# V1_3.net
KiCad netlist of a schematic drawn in Altium Designer
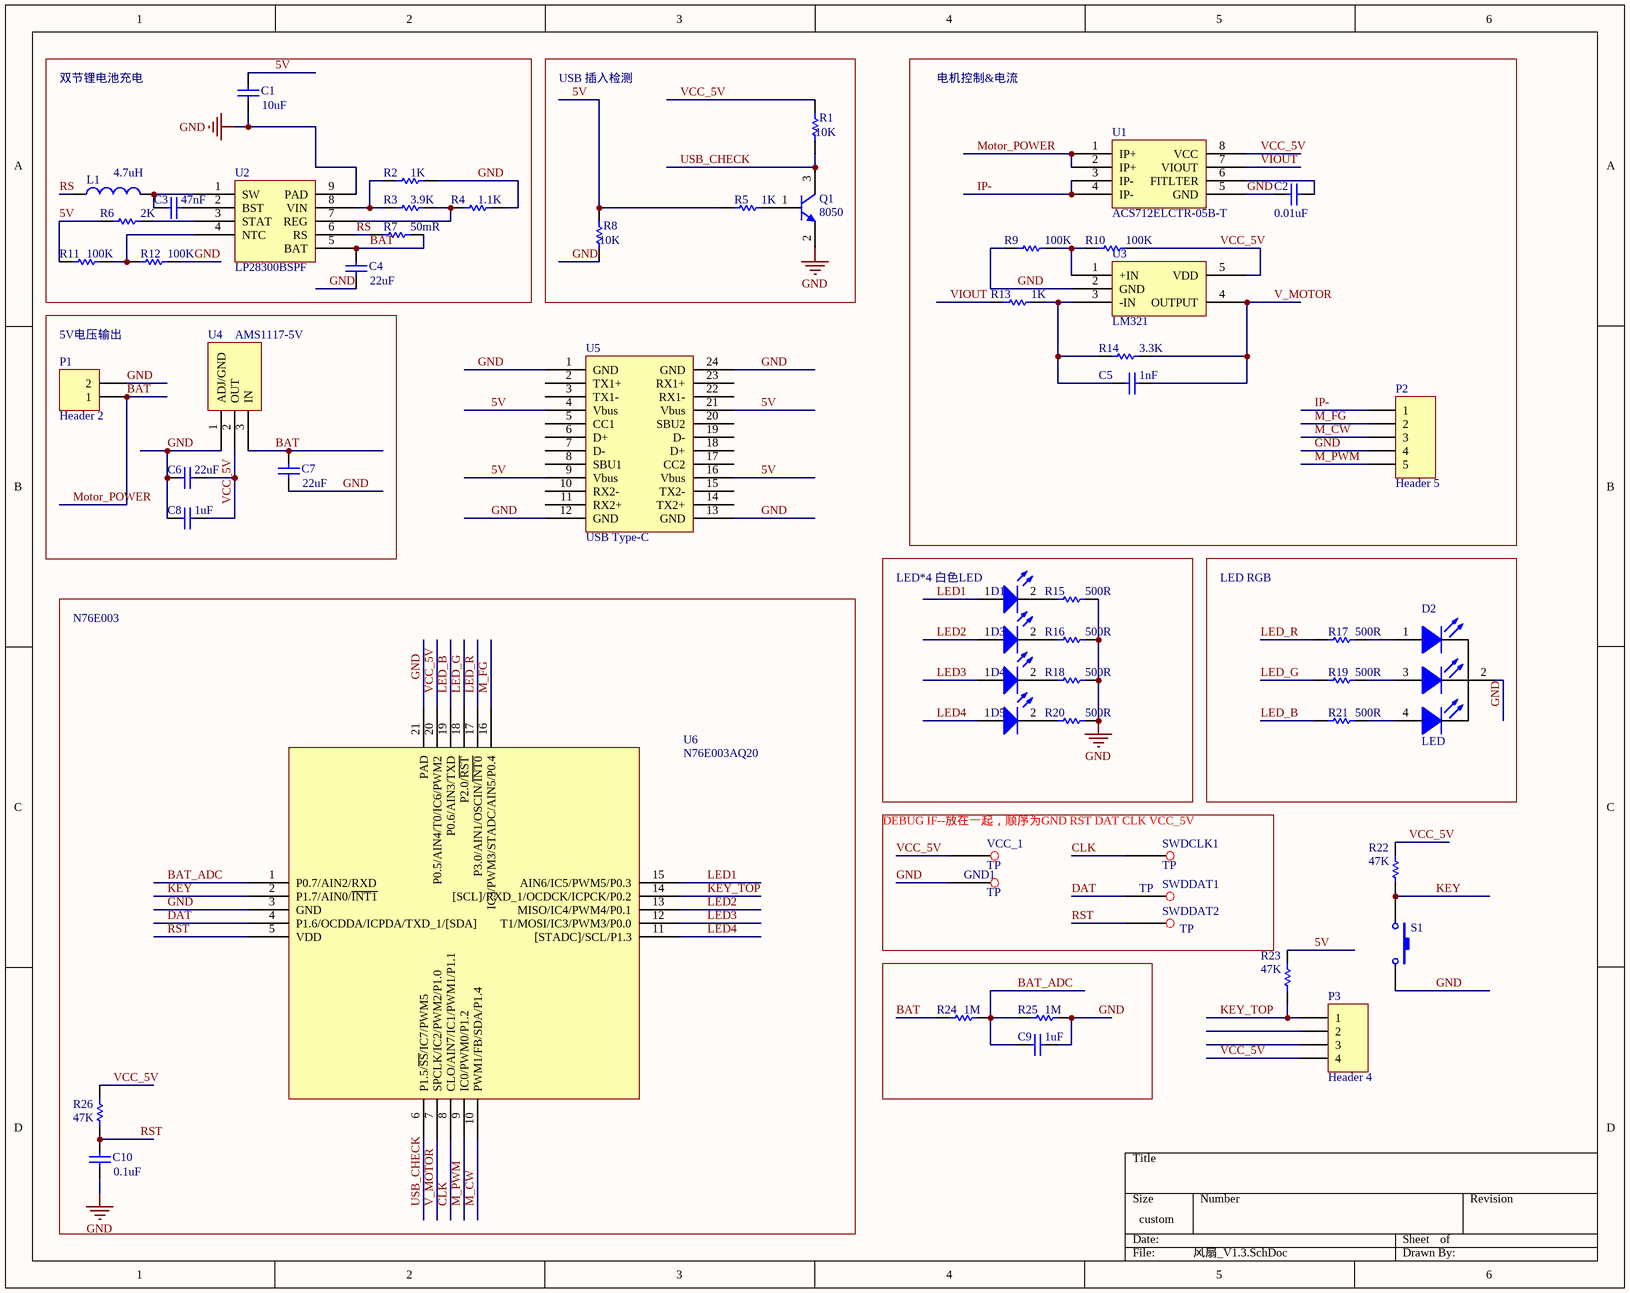
[diagram p0: 风扇_V1.3.SchDoc]

(export (version "E")
  (design (tool "Eeschema 10.0.6"))
  (components
    (comp (ref "C1")
      (value "10uF")
      (footprint "C-0805")
      (description "Capacitor")
      (fields (field (name "PUBLISHER") "Altium Limited"))
      (libsource (lib "Miscellaneous Devices") (part "Cap"))
    )
    (comp (ref "C2")
      (value "0.01uF")
      (footprint "C-0603")
      (description "Capacitor")
      (fields (field (name "PUBLISHER") "Altium Limited"))
      (libsource (lib "Miscellaneous Devices") (part "Cap"))
    )
    (comp (ref "C3")
      (value "47nF")
      (footprint "C-0603")
      (description "Capacitor")
      (fields (field (name "PUBLISHER") "Altium Limited"))
      (libsource (lib "Miscellaneous Devices") (part "Cap"))
    )
    (comp (ref "C4")
      (value "22uF")
      (footprint "C-0805")
      (description "Capacitor")
      (fields (field (name "PUBLISHER") "Altium Limited"))
      (libsource (lib "Miscellaneous Devices") (part "Cap"))
    )
    (comp (ref "C5")
      (value "1nF")
      (footprint "C-0603")
      (description "Capacitor")
      (fields (field (name "PUBLISHER") "Altium Limited"))
      (libsource (lib "Miscellaneous Devices") (part "Cap"))
    )
    (comp (ref "C6")
      (value "22uF")
      (footprint "C-0805")
      (description "Capacitor")
      (fields (field (name "PUBLISHER") "Altium Limited"))
      (libsource (lib "Miscellaneous Devices") (part "Cap"))
    )
    (comp (ref "C7")
      (value "22uF")
      (footprint "C-0805")
      (description "Capacitor")
      (fields (field (name "PUBLISHER") "Altium Limited"))
      (libsource (lib "Miscellaneous Devices") (part "Cap"))
    )
    (comp (ref "C8")
      (value "1uF")
      (footprint "C-0603")
      (description "Capacitor")
      (fields (field (name "PUBLISHER") "Altium Limited"))
      (libsource (lib "Miscellaneous Devices") (part "Cap"))
    )
    (comp (ref "C9")
      (value "1uF")
      (footprint "C-0603")
      (description "Capacitor")
      (fields (field (name "PUBLISHER") "Altium Limited"))
      (libsource (lib "Miscellaneous Devices") (part "Cap"))
    )
    (comp (ref "C10")
      (value "0.1uF")
      (footprint "C-0603")
      (description "Capacitor")
      (fields (field (name "PUBLISHER") "Altium Limited"))
      (libsource (lib "Miscellaneous Devices") (part "Cap"))
    )
    (comp (ref "D1")
      (value "LED0")
      (footprint "LED-0603")
      (description "Typical INFRARED GaAs LED")
      (fields (field (name "PUBLISHER") "Altium Limited"))
      (libsource (lib "Miscellaneous Devices") (part "LED0"))
    )
    (comp (ref "D2") (value "LED") (footprint "0603*2-LED") (libsource (lib "SA2") (part "LED")))
    (comp (ref "D3")
      (value "LED0")
      (footprint "LED-0603")
      (description "Typical INFRARED GaAs LED")
      (fields (field (name "PUBLISHER") "Altium Limited"))
      (libsource (lib "Miscellaneous Devices") (part "LED0"))
    )
    (comp (ref "D4")
      (value "LED0")
      (footprint "LED-0603")
      (description "Typical INFRARED GaAs LED")
      (fields (field (name "PUBLISHER") "Altium Limited"))
      (libsource (lib "Miscellaneous Devices") (part "LED0"))
    )
    (comp (ref "D5")
      (value "LED0")
      (footprint "LED-0603")
      (description "Typical INFRARED GaAs LED")
      (fields (field (name "PUBLISHER") "Altium Limited"))
      (libsource (lib "Miscellaneous Devices") (part "LED0"))
    )
    (comp (ref "GND1") (value "TP") (footprint "TP-1.5") (libsource (lib "Others_IC_SCH_LIB") (part "TP")))
    (comp (ref "L1")
      (value "4.7uH")
      (footprint "L-SMD")
      (description "Inductor")
      (fields (field (name "PUBLISHER") "Altium Limited"))
      (libsource (lib "Miscellaneous Devices") (part "Inductor"))
    )
    (comp (ref "P1")
      (value "Header 2")
      (footprint "HDR1X2")
      (description "Header, 2-Pin")
      (fields (field (name "PUBLISHER") "Altium Limited"))
      (libsource (lib "Miscellaneous Connectors") (part "Header 2"))
    )
    (comp (ref "P2")
      (value "Header 5")
      (footprint "HDR1X5")
      (description "Header, 5-Pin")
      (fields (field (name "PUBLISHER") "Altium Limited"))
      (libsource (lib "Miscellaneous Connectors") (part "Header 5"))
    )
    (comp (ref "P3")
      (value "Header 4")
      (footprint "HDR1X4")
      (description "Header, 4-Pin")
      (fields (field (name "PUBLISHER") "Altium Limited"))
      (libsource (lib "Miscellaneous Connectors") (part "Header 4"))
    )
    (comp (ref "Q1")
      (value "8050")
      (footprint "SOT-23")
      (description "NPN Bipolar Transistor")
      (fields (field (name "PUBLISHER") "Altium Limited"))
      (libsource (lib "Miscellaneous Devices") (part "NPN"))
    )
    (comp (ref "R1")
      (value "10K")
      (footprint "R-0603")
      (description "Resistor")
      (fields (field (name "PUBLISHER") "Altium Limited"))
      (libsource (lib "Miscellaneous Devices") (part "Res1"))
    )
    (comp (ref "R2")
      (value "1K")
      (footprint "R-0603")
      (description "Resistor")
      (fields (field (name "PUBLISHER") "Altium Limited"))
      (libsource (lib "Miscellaneous Devices") (part "Res1"))
    )
    (comp (ref "R3")
      (value "3.9K")
      (footprint "R-0603")
      (description "Resistor")
      (fields (field (name "PUBLISHER") "Altium Limited"))
      (libsource (lib "Miscellaneous Devices") (part "Res1"))
    )
    (comp (ref "R4")
      (value "1.1K")
      (footprint "R-0603")
      (description "Resistor")
      (fields (field (name "PUBLISHER") "Altium Limited"))
      (libsource (lib "Miscellaneous Devices") (part "Res1"))
    )
    (comp (ref "R5")
      (value "1K")
      (footprint "R-0603")
      (description "Resistor")
      (fields (field (name "PUBLISHER") "Altium Limited"))
      (libsource (lib "Miscellaneous Devices") (part "Res1"))
    )
    (comp (ref "R6")
      (value "2K")
      (footprint "R-0603")
      (description "Resistor")
      (fields (field (name "PUBLISHER") "Altium Limited"))
      (libsource (lib "Miscellaneous Devices") (part "Res1"))
    )
    (comp (ref "R7")
      (value "50mR")
      (footprint "R-0603")
      (description "Resistor")
      (fields (field (name "PUBLISHER") "Altium Limited"))
      (libsource (lib "Miscellaneous Devices") (part "Res1"))
    )
    (comp (ref "R8")
      (value "10K")
      (footprint "R-0603")
      (description "Resistor")
      (fields (field (name "PUBLISHER") "Altium Limited"))
      (libsource (lib "Miscellaneous Devices") (part "Res1"))
    )
    (comp (ref "R9")
      (value "100K")
      (footprint "R-0603")
      (description "Resistor")
      (fields (field (name "PUBLISHER") "Altium Limited"))
      (libsource (lib "Miscellaneous Devices") (part "Res1"))
    )
    (comp (ref "R10")
      (value "100K")
      (footprint "R-0603")
      (description "Resistor")
      (fields (field (name "PUBLISHER") "Altium Limited"))
      (libsource (lib "Miscellaneous Devices") (part "Res1"))
    )
    (comp (ref "R11")
      (value "100K")
      (footprint "R-0603")
      (description "Resistor")
      (fields (field (name "PUBLISHER") "Altium Limited"))
      (libsource (lib "Miscellaneous Devices") (part "Res1"))
    )
    (comp (ref "R12")
      (value "100K")
      (footprint "R-0603")
      (description "Resistor")
      (fields (field (name "PUBLISHER") "Altium Limited"))
      (libsource (lib "Miscellaneous Devices") (part "Res1"))
    )
    (comp (ref "R13")
      (value "1K")
      (footprint "R-0603")
      (description "Resistor")
      (fields (field (name "PUBLISHER") "Altium Limited"))
      (libsource (lib "Miscellaneous Devices") (part "Res1"))
    )
    (comp (ref "R14")
      (value "3.3K")
      (footprint "R-0603")
      (description "Resistor")
      (fields (field (name "PUBLISHER") "Altium Limited"))
      (libsource (lib "Miscellaneous Devices") (part "Res1"))
    )
    (comp (ref "R15")
      (value "500R")
      (footprint "R-0603")
      (description "Resistor")
      (fields (field (name "PUBLISHER") "Altium Limited"))
      (libsource (lib "Miscellaneous Devices") (part "Res1"))
    )
    (comp (ref "R16")
      (value "500R")
      (footprint "R-0603")
      (description "Resistor")
      (fields (field (name "PUBLISHER") "Altium Limited"))
      (libsource (lib "Miscellaneous Devices") (part "Res1"))
    )
    (comp (ref "R17")
      (value "500R")
      (footprint "R-0603")
      (description "Resistor")
      (fields (field (name "PUBLISHER") "Altium Limited"))
      (libsource (lib "Miscellaneous Devices") (part "Res1"))
    )
    (comp (ref "R18")
      (value "500R")
      (footprint "R-0603")
      (description "Resistor")
      (fields (field (name "PUBLISHER") "Altium Limited"))
      (libsource (lib "Miscellaneous Devices") (part "Res1"))
    )
    (comp (ref "R19")
      (value "500R")
      (footprint "R-0603")
      (description "Resistor")
      (fields (field (name "PUBLISHER") "Altium Limited"))
      (libsource (lib "Miscellaneous Devices") (part "Res1"))
    )
    (comp (ref "R20")
      (value "500R")
      (footprint "R-0603")
      (description "Resistor")
      (fields (field (name "PUBLISHER") "Altium Limited"))
      (libsource (lib "Miscellaneous Devices") (part "Res1"))
    )
    (comp (ref "R21")
      (value "500R")
      (footprint "R-0603")
      (description "Resistor")
      (fields (field (name "PUBLISHER") "Altium Limited"))
      (libsource (lib "Miscellaneous Devices") (part "Res1"))
    )
    (comp (ref "R22")
      (value "47K")
      (footprint "R-0603")
      (description "Resistor")
      (fields (field (name "PUBLISHER") "Altium Limited"))
      (libsource (lib "Miscellaneous Devices") (part "Res1"))
    )
    (comp (ref "R23")
      (value "47K")
      (footprint "R-0603")
      (description "Resistor")
      (fields (field (name "PUBLISHER") "Altium Limited"))
      (libsource (lib "Miscellaneous Devices") (part "Res1"))
    )
    (comp (ref "R24")
      (value "1M")
      (footprint "R-0603")
      (description "Resistor")
      (fields (field (name "PUBLISHER") "Altium Limited"))
      (libsource (lib "Miscellaneous Devices") (part "Res1"))
    )
    (comp (ref "R25")
      (value "1M")
      (footprint "R-0603")
      (description "Resistor")
      (fields (field (name "PUBLISHER") "Altium Limited"))
      (libsource (lib "Miscellaneous Devices") (part "Res1"))
    )
    (comp (ref "R26")
      (value "47K")
      (footprint "R-0603")
      (description "Resistor")
      (fields (field (name "PUBLISHER") "Altium Limited"))
      (libsource (lib "Miscellaneous Devices") (part "Res1"))
    )
    (comp (ref "S1")
      (value "SW-PB")
      (footprint "SW-6*6*4.3")
      (description "Switch")
      (fields (field (name "PUBLISHER") "Altium Limited"))
      (libsource (lib "Miscellaneous Devices") (part "SW-PB"))
    )
    (comp (ref "SWDCLK1") (value "TP") (footprint "TP-1.5") (libsource (lib "Others_IC_SCH_LIB") (part "TP")))
    (comp (ref "SWDDAT1") (value "TP") (footprint "TP-1.5") (libsource (lib "Others_IC_SCH_LIB") (part "TP")))
    (comp (ref "SWDDAT2") (value "TP") (footprint "TP-1.5") (libsource (lib "Others_IC_SCH_LIB") (part "TP")))
    (comp (ref "U1")
      (value "ACS712ELCTR-05B-T")
      (footprint "SOIC8")
      (libsource (lib "Others_IC_SCH_LIB") (part "ACS712ELCTR-05B-T"))
    )
    (comp (ref "U2")
      (value "LP28300BSPF")
      (footprint "ESOP8")
      (libsource (lib "Others_IC_SCH_LIB") (part "LP28300BSPF"))
    )
    (comp (ref "U3")
      (value "LM321")
      (footprint "SOT-23-5")
      (libsource (lib "Others_IC_SCH_LIB") (part "LM321"))
    )
    (comp (ref "U4")
      (value "AMS1117-5V")
      (footprint "SOT-223")
      (libsource (lib "Others_IC_SCH_LIB") (part "AMS1117"))
    )
    (comp (ref "U5")
      (value "USB Type-C")
      (footprint "USB-type C")
      (libsource (lib "Others_IC_SCH_LIB") (part "USB Type-C"))
    )
    (comp (ref "U6")
      (value "N76E003AQ20")
      (footprint "QFN-20 0.4mm")
      (libsource (lib "Others_IC_SCH_LIB") (part "N76E003AQ20"))
    )
    (comp (ref "VCC_1") (value "TP") (footprint "TP-1.5") (libsource (lib "Others_IC_SCH_LIB") (part "TP")))
  )
  (nets
    (net (code "1") (name "/5V") (class "Default")
      (node (ref "C1") (pin "1") (pinfunction "1_1") (pintype "passive"))
      (node (ref "R11") (pin "2") (pinfunction "2_2") (pintype "passive"))
      (node (ref "R23") (pin "2") (pinfunction "2_2") (pintype "passive"))
      (node (ref "R5") (pin "1") (pinfunction "1_1") (pintype "passive"))
      (node (ref "R6") (pin "2") (pinfunction "2_2") (pintype "passive"))
      (node (ref "R8") (pin "1") (pinfunction "1_1") (pintype "passive"))
      (node (ref "U5") (pin "16") (pinfunction "Vbus_16") (pintype "passive"))
      (node (ref "U5") (pin "21") (pinfunction "Vbus_21") (pintype "passive"))
      (node (ref "U5") (pin "4") (pinfunction "Vbus_4") (pintype "passive"))
      (node (ref "U5") (pin "9") (pinfunction "Vbus_9") (pintype "passive"))
    )
    (net (code "2") (name "/BAT") (class "Default")
      (node (ref "C4") (pin "1") (pinfunction "1_1") (pintype "passive"))
      (node (ref "C7") (pin "2") (pinfunction "2_2") (pintype "passive"))
      (node (ref "P1") (pin "1") (pinfunction "1_1") (pintype "passive"))
      (node (ref "R24") (pin "1") (pinfunction "1_1") (pintype "passive"))
      (node (ref "R7") (pin "1") (pinfunction "1_1") (pintype "passive"))
      (node (ref "U1") (pin "1") (pinfunction "IP+_1") (pintype "passive"))
      (node (ref "U1") (pin "2") (pinfunction "IP+_2") (pintype "passive"))
      (node (ref "U2") (pin "5") (pinfunction "BAT_5") (pintype "passive"))
      (node (ref "U4") (pin "3") (pinfunction "IN_3") (pintype "passive"))
    )
    (net (code "3") (name "/BAT_ADC") (class "Default")
      (node (ref "C9") (pin "2") (pinfunction "2_2") (pintype "passive"))
      (node (ref "R24") (pin "2") (pinfunction "2_2") (pintype "passive"))
      (node (ref "R25") (pin "1") (pinfunction "1_1") (pintype "passive"))
      (node (ref "U6") (pin "1") (pinfunction "P0.7/AIN2/RXD_1") (pintype "passive"))
    )
    (net (code "4") (name "/CLK") (class "Default")
      (node (ref "SWDCLK1") (pin "1") (pinfunction "1_1") (pintype "passive"))
      (node (ref "U6") (pin "8") (pinfunction "CLO/AIN7/IC1/PWM1/P1.1_8") (pintype "passive"))
    )
    (net (code "5") (name "/DAT") (class "Default")
      (node (ref "SWDDAT1") (pin "1") (pinfunction "1_1") (pintype "passive"))
      (node (ref "U6") (pin "4") (pinfunction "P1.6/OCDDA/ICPDA/TXD_1/[SDA]_4") (pintype "passive"))
    )
    (net (code "6") (name "/IP-") (class "Default")
      (node (ref "P2") (pin "1") (pinfunction "1_1") (pintype "passive"))
      (node (ref "U1") (pin "3") (pinfunction "IP-_3") (pintype "passive"))
      (node (ref "U1") (pin "4") (pinfunction "IP-_4") (pintype "passive"))
    )
    (net (code "7") (name "/KEY") (class "Default")
      (node (ref "R22") (pin "1") (pinfunction "1_1") (pintype "passive"))
      (node (ref "S1") (pin "1") (pinfunction "1_1") (pintype "passive"))
      (node (ref "U6") (pin "2") (pinfunction "P1.7/AIN0/~{INT1}_2") (pintype "passive"))
    )
    (net (code "8") (name "/KEY_TOP") (class "Default")
      (node (ref "P3") (pin "1") (pinfunction "1_1") (pintype "passive"))
      (node (ref "R23") (pin "1") (pinfunction "1_1") (pintype "passive"))
      (node (ref "U6") (pin "14") (pinfunction "[SCL]/RXD_1/OCDCK/ICPCK/P0.2_14") (pintype "passive"))
    )
    (net (code "9") (name "/LED1") (class "Default")
      (node (ref "D1") (pin "1") (pinfunction "A_1") (pintype "passive"))
      (node (ref "U6") (pin "15") (pinfunction "AIN6/IC5/PWM5/P0.3_15") (pintype "passive"))
    )
    (net (code "10") (name "/LED2") (class "Default")
      (node (ref "D3") (pin "1") (pinfunction "A_1") (pintype "passive"))
      (node (ref "U6") (pin "13") (pinfunction "MISO/IC4/PWM4/P0.1_13") (pintype "passive"))
    )
    (net (code "11") (name "/LED3") (class "Default")
      (node (ref "D4") (pin "1") (pinfunction "A_1") (pintype "passive"))
      (node (ref "U6") (pin "12") (pinfunction "T1/MOSI/IC3/PWM3/P0.0_12") (pintype "passive"))
    )
    (net (code "12") (name "/LED4") (class "Default")
      (node (ref "D5") (pin "1") (pinfunction "A_1") (pintype "passive"))
      (node (ref "U6") (pin "11") (pinfunction "[STADC]/SCL/P1.3_11") (pintype "passive"))
    )
    (net (code "13") (name "/LED_B") (class "Default")
      (node (ref "R21") (pin "1") (pinfunction "1_1") (pintype "passive"))
      (node (ref "U6") (pin "19") (pinfunction "P0.6/AIN3/TXD_19") (pintype "passive"))
    )
    (net (code "14") (name "/LED_G") (class "Default")
      (node (ref "R19") (pin "1") (pinfunction "1_1") (pintype "passive"))
      (node (ref "U6") (pin "18") (pinfunction "P2.0/~{RST}_18") (pintype "passive"))
    )
    (net (code "15") (name "/LED_R") (class "Default")
      (node (ref "R17") (pin "1") (pinfunction "1_1") (pintype "passive"))
      (node (ref "U6") (pin "17") (pinfunction "P3.0/AIN1/OSCIN/~{INT0}_17") (pintype "passive"))
    )
    (net (code "16") (name "/M_CW") (class "Default")
      (node (ref "P2") (pin "3") (pinfunction "3_3") (pintype "passive"))
      (node (ref "U6") (pin "10") (pinfunction "PWM1/FB/SDA/P1.4_10") (pintype "passive"))
    )
    (net (code "17") (name "/M_FG") (class "Default")
      (node (ref "P2") (pin "2") (pinfunction "2_2") (pintype "passive"))
      (node (ref "U6") (pin "16") (pinfunction "IC3/PWM3/STADC/AIN5/P0.4_16") (pintype "passive"))
    )
    (net (code "18") (name "/M_PWM") (class "Default")
      (node (ref "P2") (pin "5") (pinfunction "5_5") (pintype "passive"))
      (node (ref "U6") (pin "9") (pinfunction "IC0/PWM0/P1.2_9") (pintype "passive"))
    )
    (net (code "19") (name "/RS") (class "Default")
      (node (ref "L1") (pin "1") (pinfunction "1_1") (pintype "passive"))
      (node (ref "R7") (pin "2") (pinfunction "2_2") (pintype "passive"))
      (node (ref "U2") (pin "6") (pinfunction "RS_6") (pintype "passive"))
    )
    (net (code "20") (name "/RST") (class "Default")
      (node (ref "C10") (pin "2") (pinfunction "2_2") (pintype "passive"))
      (node (ref "R26") (pin "1") (pinfunction "1_1") (pintype "passive"))
      (node (ref "SWDDAT2") (pin "1") (pinfunction "1_1") (pintype "passive"))
      (node (ref "U6") (pin "5") (pinfunction "VDD_5") (pintype "passive"))
    )
    (net (code "21") (name "/USB_CHECK") (class "Default")
      (node (ref "Q1") (pin "3") (pinfunction "C_3") (pintype "passive"))
      (node (ref "R1") (pin "1") (pinfunction "1_1") (pintype "passive"))
      (node (ref "U6") (pin "6") (pinfunction "P1.5/~{SS}/IC7/PWM5_6") (pintype "passive"))
    )
    (net (code "22") (name "/VCC_5V") (class "Default")
      (node (ref "C6") (pin "2") (pinfunction "2_2") (pintype "passive"))
      (node (ref "C8") (pin "2") (pinfunction "2_2") (pintype "passive"))
      (node (ref "P3") (pin "4") (pinfunction "4_4") (pintype "passive"))
      (node (ref "R1") (pin "2") (pinfunction "2_2") (pintype "passive"))
      (node (ref "R10") (pin "2") (pinfunction "2_2") (pintype "passive"))
      (node (ref "R22") (pin "2") (pinfunction "2_2") (pintype "passive"))
      (node (ref "R26") (pin "2") (pinfunction "2_2") (pintype "passive"))
      (node (ref "U1") (pin "8") (pinfunction "VCC_8") (pintype "passive"))
      (node (ref "U3") (pin "5") (pinfunction "VDD_5") (pintype "passive"))
      (node (ref "U4") (pin "2") (pinfunction "OUT_2") (pintype "passive"))
      (node (ref "U6") (pin "20") (pinfunction "P0.5/AIN4/T0/IC6/PWM2_20") (pintype "passive"))
      (node (ref "VCC_1") (pin "1") (pinfunction "1_1") (pintype "passive"))
    )
    (net (code "23") (name "/VIOUT") (class "Default")
      (node (ref "R13") (pin "1") (pinfunction "1_1") (pintype "passive"))
      (node (ref "U1") (pin "7") (pinfunction "VIOUT_7") (pintype "passive"))
    )
    (net (code "24") (name "/V_MOTOR") (class "Default")
      (node (ref "C5") (pin "1") (pinfunction "1_1") (pintype "passive"))
      (node (ref "R14") (pin "2") (pinfunction "2_2") (pintype "passive"))
      (node (ref "U3") (pin "4") (pinfunction "OUTPUT_4") (pintype "passive"))
      (node (ref "U6") (pin "7") (pinfunction "SPCLK/IC2/PWM2/P1.0_7") (pintype "passive"))
    )
    (net (code "25") (name "GND") (class "Default")
      (node (ref "C1") (pin "2") (pinfunction "2_2") (pintype "passive"))
      (node (ref "C10") (pin "1") (pinfunction "1_1") (pintype "passive"))
      (node (ref "C2") (pin "2") (pinfunction "2_2") (pintype "passive"))
      (node (ref "C4") (pin "2") (pinfunction "2_2") (pintype "passive"))
      (node (ref "C6") (pin "1") (pinfunction "1_1") (pintype "passive"))
      (node (ref "C7") (pin "1") (pinfunction "1_1") (pintype "passive"))
      (node (ref "C8") (pin "1") (pinfunction "1_1") (pintype "passive"))
      (node (ref "C9") (pin "1") (pinfunction "1_1") (pintype "passive"))
      (node (ref "D2") (pin "2") (pinfunction "2_2") (pintype "passive"))
      (node (ref "GND1") (pin "1") (pinfunction "1_1") (pintype "passive"))
      (node (ref "P1") (pin "2") (pinfunction "2_2") (pintype "passive"))
      (node (ref "P2") (pin "4") (pinfunction "4_4") (pintype "passive"))
      (node (ref "Q1") (pin "2") (pinfunction "E_2") (pintype "passive"))
      (node (ref "R12") (pin "1") (pinfunction "1_1") (pintype "passive"))
      (node (ref "R15") (pin "2") (pinfunction "2_2") (pintype "passive"))
      (node (ref "R16") (pin "2") (pinfunction "2_2") (pintype "passive"))
      (node (ref "R18") (pin "2") (pinfunction "2_2") (pintype "passive"))
      (node (ref "R2") (pin "1") (pinfunction "1_1") (pintype "passive"))
      (node (ref "R20") (pin "2") (pinfunction "2_2") (pintype "passive"))
      (node (ref "R25") (pin "2") (pinfunction "2_2") (pintype "passive"))
      (node (ref "R4") (pin "1") (pinfunction "1_1") (pintype "passive"))
      (node (ref "R8") (pin "2") (pinfunction "2_2") (pintype "passive"))
      (node (ref "R9") (pin "1") (pinfunction "1_1") (pintype "passive"))
      (node (ref "S1") (pin "2") (pinfunction "2_2") (pintype "passive"))
      (node (ref "U1") (pin "5") (pinfunction "GND_5") (pintype "passive"))
      (node (ref "U2") (pin "9") (pinfunction "PAD_9") (pintype "passive"))
      (node (ref "U3") (pin "2") (pinfunction "GND_2") (pintype "passive"))
      (node (ref "U4") (pin "1") (pinfunction "ADJ/GND_1") (pintype "passive"))
      (node (ref "U5") (pin "1") (pinfunction "GND_1") (pintype "passive"))
      (node (ref "U5") (pin "12") (pinfunction "GND_12") (pintype "passive"))
      (node (ref "U5") (pin "13") (pinfunction "GND_13") (pintype "passive"))
      (node (ref "U5") (pin "24") (pinfunction "GND_24") (pintype "passive"))
      (node (ref "U6") (pin "21") (pinfunction "PAD_21") (pintype "passive"))
      (node (ref "U6") (pin "3") (pinfunction "GND_3") (pintype "passive"))
    )
    (net (code "26") (name "Net-(D1-K)") (class "Default")
      (node (ref "D1") (pin "2") (pinfunction "K_2") (pintype "passive"))
      (node (ref "R15") (pin "1") (pinfunction "1_1") (pintype "passive"))
    )
    (net (code "27") (name "Net-(D2-Pad1)") (class "Default")
      (node (ref "D2") (pin "1") (pinfunction "1_1") (pintype "passive"))
      (node (ref "R17") (pin "2") (pinfunction "2_2") (pintype "passive"))
    )
    (net (code "28") (name "Net-(D2-Pad3)") (class "Default")
      (node (ref "D2") (pin "3") (pinfunction "3_3") (pintype "passive"))
      (node (ref "R19") (pin "2") (pinfunction "2_2") (pintype "passive"))
    )
    (net (code "29") (name "Net-(D2-Pad4)") (class "Default")
      (node (ref "D2") (pin "4") (pinfunction "4_4") (pintype "passive"))
      (node (ref "R21") (pin "2") (pinfunction "2_2") (pintype "passive"))
    )
    (net (code "30") (name "Net-(D3-K)") (class "Default")
      (node (ref "D3") (pin "2") (pinfunction "K_2") (pintype "passive"))
      (node (ref "R16") (pin "1") (pinfunction "1_1") (pintype "passive"))
    )
    (net (code "31") (name "Net-(D4-K)") (class "Default")
      (node (ref "D4") (pin "2") (pinfunction "K_2") (pintype "passive"))
      (node (ref "R18") (pin "1") (pinfunction "1_1") (pintype "passive"))
    )
    (net (code "32") (name "Net-(D5-K)") (class "Default")
      (node (ref "D5") (pin "2") (pinfunction "K_2") (pintype "passive"))
      (node (ref "R20") (pin "1") (pinfunction "1_1") (pintype "passive"))
    )
    (net (code "33") (name "Net-(Q1-B)") (class "Default")
      (node (ref "Q1") (pin "1") (pinfunction "B_1") (pintype "passive"))
      (node (ref "R5") (pin "2") (pinfunction "2_2") (pintype "passive"))
    )
    (net (code "34") (name "Net-(U1-FITLTER)") (class "Default")
      (node (ref "C2") (pin "1") (pinfunction "1_1") (pintype "passive"))
      (node (ref "U1") (pin "6") (pinfunction "FITLTER_6") (pintype "passive"))
    )
    (net (code "35") (name "Net-(U2-BST)") (class "Default")
      (node (ref "C3") (pin "2") (pinfunction "2_2") (pintype "passive"))
      (node (ref "U2") (pin "2") (pinfunction "BST_2") (pintype "passive"))
    )
    (net (code "36") (name "Net-(U2-NTC)") (class "Default")
      (node (ref "R11") (pin "1") (pinfunction "1_1") (pintype "passive"))
      (node (ref "R12") (pin "2") (pinfunction "2_2") (pintype "passive"))
      (node (ref "U2") (pin "4") (pinfunction "NTC_4") (pintype "passive"))
    )
    (net (code "37") (name "Net-(U2-REG)") (class "Default")
      (node (ref "R3") (pin "1") (pinfunction "1_1") (pintype "passive"))
      (node (ref "R4") (pin "2") (pinfunction "2_2") (pintype "passive"))
      (node (ref "U2") (pin "7") (pinfunction "REG_7") (pintype "passive"))
    )
    (net (code "38") (name "Net-(U2-STAT)") (class "Default")
      (node (ref "R6") (pin "1") (pinfunction "1_1") (pintype "passive"))
      (node (ref "U2") (pin "3") (pinfunction "STAT_3") (pintype "passive"))
    )
    (net (code "39") (name "Net-(U2-SW)") (class "Default")
      (node (ref "C3") (pin "1") (pinfunction "1_1") (pintype "passive"))
      (node (ref "L1") (pin "2") (pinfunction "2_2") (pintype "passive"))
      (node (ref "U2") (pin "1") (pinfunction "SW_1") (pintype "passive"))
    )
    (net (code "40") (name "Net-(U2-VIN)") (class "Default")
      (node (ref "R2") (pin "2") (pinfunction "2_2") (pintype "passive"))
      (node (ref "R3") (pin "2") (pinfunction "2_2") (pintype "passive"))
      (node (ref "U2") (pin "8") (pinfunction "VIN_8") (pintype "passive"))
    )
    (net (code "41") (name "Net-(U3-+IN)") (class "Default")
      (node (ref "R10") (pin "1") (pinfunction "1_1") (pintype "passive"))
      (node (ref "R9") (pin "2") (pinfunction "2_2") (pintype "passive"))
      (node (ref "U3") (pin "1") (pinfunction "+IN_1") (pintype "passive"))
    )
    (net (code "42") (name "Net-(U3--IN)") (class "Default")
      (node (ref "C5") (pin "2") (pinfunction "2_2") (pintype "passive"))
      (node (ref "R13") (pin "2") (pinfunction "2_2") (pintype "passive"))
      (node (ref "R14") (pin "1") (pinfunction "1_1") (pintype "passive"))
      (node (ref "U3") (pin "3") (pinfunction "-IN_3") (pintype "passive"))
    )
    (net (code "43") (name "unconnected-(P3-Pad2)") (class "Default")
      (node (ref "P3") (pin "2") (pinfunction "2_2") (pintype "passive"))
    )
    (net (code "44") (name "unconnected-(P3-Pad3)") (class "Default")
      (node (ref "P3") (pin "3") (pinfunction "3_3") (pintype "passive"))
    )
    (net (code "45") (name "unconnected-(U5-CC1-Pad5)") (class "Default")
      (node (ref "U5") (pin "5") (pinfunction "CC1_5") (pintype "passive"))
    )
    (net (code "46") (name "unconnected-(U5-CC2-Pad17)") (class "Default")
      (node (ref "U5") (pin "17") (pinfunction "CC2_17") (pintype "passive"))
    )
    (net (code "47") (name "unconnected-(U5-D+-Pad6)") (class "Default")
      (node (ref "U5") (pin "6") (pinfunction "D+_6") (pintype "passive"))
    )
    (net (code "48") (name "unconnected-(U5-D+-Pad18)") (class "Default")
      (node (ref "U5") (pin "18") (pinfunction "D+_18") (pintype "passive"))
    )
    (net (code "49") (name "unconnected-(U5-D--Pad7)") (class "Default")
      (node (ref "U5") (pin "7") (pinfunction "D-_7") (pintype "passive"))
    )
    (net (code "50") (name "unconnected-(U5-D--Pad19)") (class "Default")
      (node (ref "U5") (pin "19") (pinfunction "D-_19") (pintype "passive"))
    )
    (net (code "51") (name "unconnected-(U5-RX1+-Pad23)") (class "Default")
      (node (ref "U5") (pin "23") (pinfunction "RX1+_23") (pintype "passive"))
    )
    (net (code "52") (name "unconnected-(U5-RX1--Pad22)") (class "Default")
      (node (ref "U5") (pin "22") (pinfunction "RX1-_22") (pintype "passive"))
    )
    (net (code "53") (name "unconnected-(U5-RX2+-Pad11)") (class "Default")
      (node (ref "U5") (pin "11") (pinfunction "RX2+_11") (pintype "passive"))
    )
    (net (code "54") (name "unconnected-(U5-RX2--Pad10)") (class "Default")
      (node (ref "U5") (pin "10") (pinfunction "RX2-_10") (pintype "passive"))
    )
    (net (code "55") (name "unconnected-(U5-SBU1-Pad8)") (class "Default")
      (node (ref "U5") (pin "8") (pinfunction "SBU1_8") (pintype "passive"))
    )
    (net (code "56") (name "unconnected-(U5-SBU2-Pad20)") (class "Default")
      (node (ref "U5") (pin "20") (pinfunction "SBU2_20") (pintype "passive"))
    )
    (net (code "57") (name "unconnected-(U5-TX1+-Pad2)") (class "Default")
      (node (ref "U5") (pin "2") (pinfunction "TX1+_2") (pintype "passive"))
    )
    (net (code "58") (name "unconnected-(U5-TX1--Pad3)") (class "Default")
      (node (ref "U5") (pin "3") (pinfunction "TX1-_3") (pintype "passive"))
    )
    (net (code "59") (name "unconnected-(U5-TX2+-Pad14)") (class "Default")
      (node (ref "U5") (pin "14") (pinfunction "TX2+_14") (pintype "passive"))
    )
    (net (code "60") (name "unconnected-(U5-TX2--Pad15)") (class "Default")
      (node (ref "U5") (pin "15") (pinfunction "TX2-_15") (pintype "passive"))
    )
  )
)
